# 3xInputs.net
KiCad netlist of a schematic drawn in Altium Designer
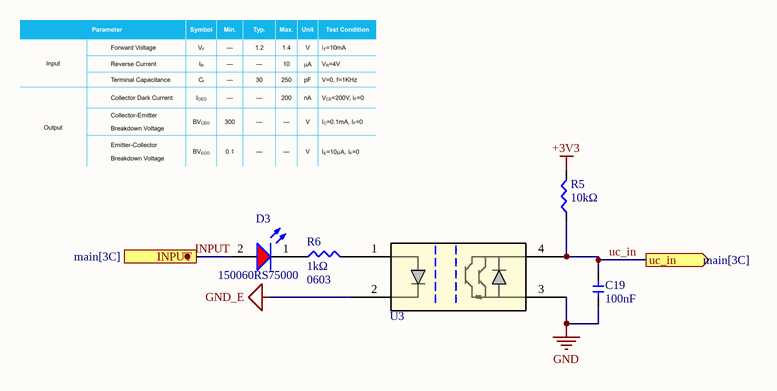
[diagram p0: 3xInputs.SchDoc]

(export (version "E")
  (design (tool "Eeschema 10.0.6"))
  (components
    (comp (ref "C19")
      (value "100nF")
      (footprint "0603_cap")
      (fields (field (name "Comment") "0603_100nF"))
      (libsource (lib "generic") (part "0603_100nF"))
    )
    (comp (ref "D3")
      (value "150060RS75000")
      (footprint "WL-SMCW_0603_150060xx75000")
      (libsource (lib "Altium Content Vault") (part "LED_Red_2A-1K"))
    )
    (comp (ref "R5")
      (value "10kΩ")
      (footprint "0603-smd")
      (fields (field (name "POWER") "W") (field (name "Comment") "0603_10K"))
      (libsource (lib "generic") (part "0603_10K"))
    )
    (comp (ref "R6")
      (value "1kΩ")
      (footprint "0603-smd")
      (fields (field (name "POWER") "W") (field (name "PACKAGE") "0603") (field (name "Comment") "0603_1K"))
      (libsource (lib "generic") (part "0603_1K"))
    )
    (comp (ref "U3")
      (value "LTV-352T")
      (footprint "IC4_LTV-352T_LTO-M")
      (description "LTV Series Single Channel 300V 3750 Vrms Transistor Output Optocoupler SMT DIP-4")
      (fields (field (name "MANUFACTURER") "Vishay Lite-On"))
      (libsource (lib "generic") (part "LTV-352T"))
    )
  )
  (nets
    (net (code "1") (name "+3V3") (class "Default")
      (node (ref "R5") (pin "2") (pinfunction "2_2") (pintype "passive"))
    )
    (net (code "2") (name "/INPUT") (class "Default")
      (node (ref "D3") (pin "2") (pinfunction "A_2") (pintype "passive"))
    )
    (net (code "3") (name "/uc_in") (class "Default")
      (node (ref "C19") (pin "2") (pinfunction "2_2") (pintype "passive"))
      (node (ref "R5") (pin "1") (pinfunction "1_1") (pintype "passive"))
      (node (ref "U3") (pin "4") (pinfunction "4_4") (pintype "passive"))
    )
    (net (code "4") (name "GND") (class "Default")
      (node (ref "C19") (pin "1") (pinfunction "1_1") (pintype "passive"))
      (node (ref "U3") (pin "3") (pinfunction "3_3") (pintype "passive"))
    )
    (net (code "5") (name "GND_E") (class "Default")
      (node (ref "U3") (pin "2") (pinfunction "2_2") (pintype "passive"))
    )
    (net (code "6") (name "Net-(D3-K)") (class "Default")
      (node (ref "D3") (pin "1") (pinfunction "K_1") (pintype "passive"))
      (node (ref "R6") (pin "1") (pinfunction "1_1") (pintype "passive"))
    )
    (net (code "7") (name "Net-(R6-Pad2)") (class "Default")
      (node (ref "R6") (pin "2") (pinfunction "2_2") (pintype "passive"))
      (node (ref "U3") (pin "1") (pinfunction "1_1") (pintype "passive"))
    )
  )
)
